# RB_Conn.net
KiCad netlist of a schematic drawn in Altium Designer
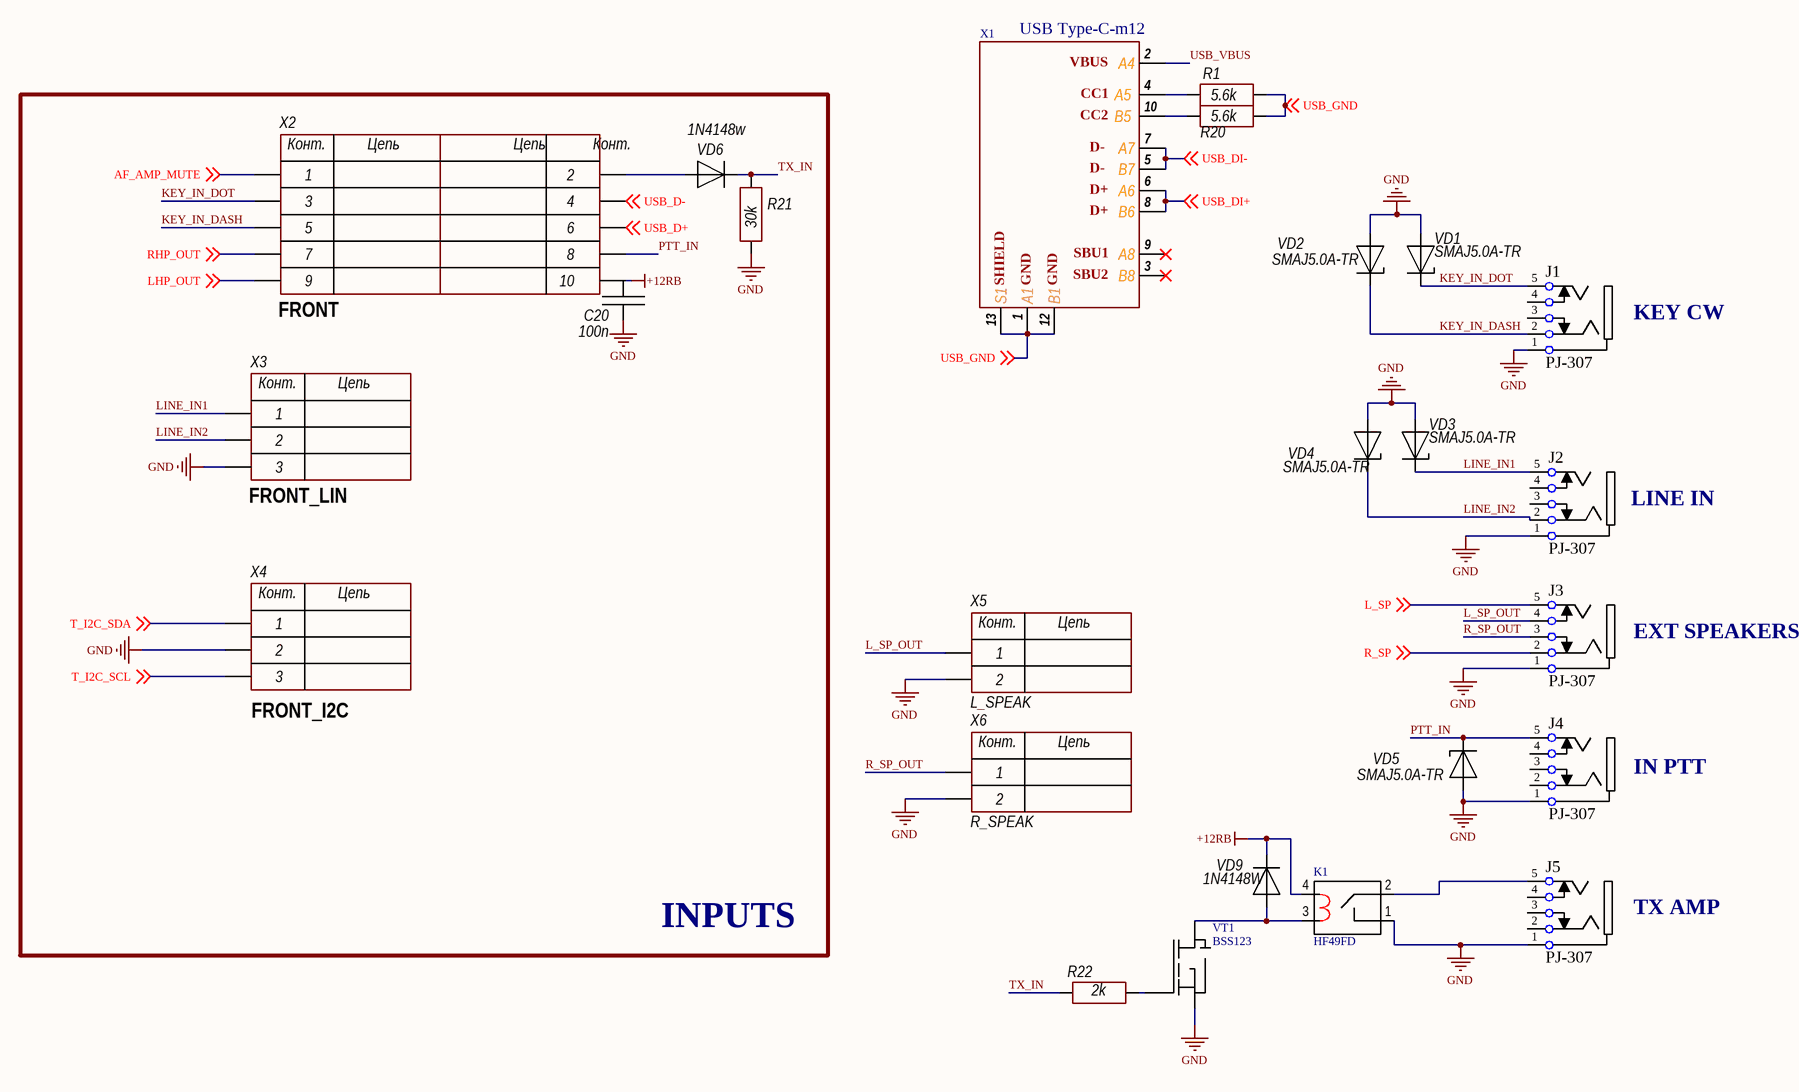
[diagram p0: RB_Conn.SchDoc]

(export (version "E")
  (design (tool "Eeschema 10.0.6"))
  (components
    (comp (ref "C20")
      (value "100n")
      (footprint "standard:CH0805C")
      (libsource (lib "Discrete") (part "Capacitor"))
    )
    (comp (ref "J1")
      (value "PJ-307")
      (footprint "PJ-307")
      (description "KEY")
      (libsource (lib "") (part "JACK_Audio-3_1"))
    )
    (comp (ref "J2")
      (value "PJ-307")
      (footprint "PJ-307")
      (description "LIN")
      (libsource (lib "Connectors") (part "JACK_Audio-3"))
    )
    (comp (ref "J3")
      (value "PJ-307")
      (footprint "PJ-307")
      (description "OUT_SPEAKERS")
      (libsource (lib "Connectors") (part "JACK_Audio-3"))
    )
    (comp (ref "J4")
      (value "PJ-307")
      (footprint "PJ-307")
      (description "PTT_IN")
      (libsource (lib "Connectors") (part "JACK_Audio-3"))
    )
    (comp (ref "J5")
      (value "PJ-307")
      (footprint "PJ-307")
      (description "TX")
      (libsource (lib "Connectors") (part "JACK_Audio-3"))
    )
    (comp (ref "K1") (value "HF49FD") (footprint "HF49FD") (libsource (lib "Relay") (part "HF49FD 012-1H12")))
    (comp (ref "R1")
      (value "5.6k")
      (footprint "standard:CH0805R")
      (libsource (lib "Discrete") (part "Resistor"))
    )
    (comp (ref "R20") (value "5.6k") (footprint "standard:CH0805R") (libsource (lib "") (part "Resistor_1")))
    (comp (ref "R21") (value "30k") (footprint "standard:CH0805R") (libsource (lib "") (part "Resistor_2")))
    (comp (ref "R22")
      (value "2k")
      (footprint "standard:CH0805R")
      (libsource (lib "Discrete") (part "Resistor"))
    )
    (comp (ref "VD1")
      (value "SMAJ5.0A-TR")
      (footprint "standard:SMA")
      (libsource (lib "Diods") (part "Diod Zener"))
    )
    (comp (ref "VD2")
      (value "SMAJ5.0A-TR")
      (footprint "standard:SMA")
      (libsource (lib "Diods") (part "Diod Zener"))
    )
    (comp (ref "VD3")
      (value "SMAJ5.0A-TR")
      (footprint "standard:SMA")
      (libsource (lib "Diods") (part "Diod Zener"))
    )
    (comp (ref "VD4")
      (value "SMAJ5.0A-TR")
      (footprint "standard:SMA")
      (libsource (lib "Diods") (part "Diod Zener"))
    )
    (comp (ref "VD5")
      (value "SMAJ5.0A-TR")
      (footprint "standard:SMA")
      (libsource (lib "Diods") (part "Diod Zener"))
    )
    (comp (ref "VD6") (value "1N4148w") (footprint "standard:SOD323") (libsource (lib "Diods") (part "Diod")))
    (comp (ref "VD9") (value "1N4148W") (footprint "standard:SOD123") (libsource (lib "Diods") (part "Diod")))
    (comp (ref "VT1") (value "BSS123") (footprint "SOT23_132") (libsource (lib "Transistor") (part "BSS123")))
    (comp (ref "X1")
      (value "USB Type-C-m12")
      (footprint "PCBComponent_1")
      (libsource (lib "USB typ-c") (part "USB-C_2.0"))
    )
    (comp (ref "X2")
      (value "FRONT")
      (footprint "custom:CON: BH-10")
      (libsource (lib "Connectors") (part "10(2)-Connector"))
    )
    (comp (ref "X3")
      (value "FRONT_LIN")
      (footprint "custom:CON: CWF-3")
      (libsource (lib "Connectors") (part "3-Connector"))
    )
    (comp (ref "X4")
      (value "FRONT_I2C")
      (footprint "custom:CON: CWF-3")
      (libsource (lib "Connectors") (part "3-Connector"))
    )
    (comp (ref "X5")
      (value "L_SPEAK")
      (footprint "custom:CON: PLS-2")
      (libsource (lib "Connectors") (part "2-Connector"))
    )
    (comp (ref "X6")
      (value "R_SPEAK")
      (footprint "custom:CON: PLS-2")
      (libsource (lib "Connectors") (part "2-Connector"))
    )
  )
  (nets
    (net (code "1") (name "+12RB") (class "Default")
      (node (ref "K1") (pin "4") (pintype "passive"))
      (node (ref "VD9") (pin "2") (pinfunction "2_2") (pintype "passive"))
      (node (ref "X2") (pin "10") (pinfunction "10_10") (pintype "power_in"))
    )
    (net (code "2") (name "/KEY_IN_DASH") (class "Default")
      (node (ref "J1") (pin "2") (pinfunction "2_2") (pintype "passive"))
      (node (ref "VD2") (pin "2") (pinfunction "C_2") (pintype "passive"))
      (node (ref "X2") (pin "5") (pinfunction "5_5") (pintype "power_in"))
    )
    (net (code "3") (name "/KEY_IN_DOT") (class "Default")
      (node (ref "J1") (pin "5") (pinfunction "5_5") (pintype "passive"))
      (node (ref "VD1") (pin "2") (pinfunction "C_2") (pintype "passive"))
      (node (ref "X2") (pin "3") (pinfunction "3_3") (pintype "passive"))
    )
    (net (code "4") (name "/LINE_IN1") (class "Default")
      (node (ref "J2") (pin "5") (pinfunction "5_5") (pintype "passive"))
      (node (ref "VD3") (pin "2") (pinfunction "C_2") (pintype "passive"))
      (node (ref "X3") (pin "1") (pinfunction "1_1") (pintype "passive"))
    )
    (net (code "5") (name "/LINE_IN2") (class "Default")
      (node (ref "J2") (pin "2") (pinfunction "2_2") (pintype "passive"))
      (node (ref "VD4") (pin "2") (pinfunction "C_2") (pintype "passive"))
      (node (ref "X3") (pin "2") (pinfunction "2_2") (pintype "passive"))
    )
    (net (code "6") (name "/L_SP_OUT") (class "Default")
      (node (ref "J3") (pin "4") (pinfunction "4_4") (pintype "passive"))
      (node (ref "X5") (pin "1") (pinfunction "1_1") (pintype "passive"))
    )
    (net (code "7") (name "/PTT_IN") (class "Default")
      (node (ref "J4") (pin "5") (pinfunction "5_5") (pintype "passive"))
      (node (ref "VD5") (pin "2") (pinfunction "C_2") (pintype "passive"))
      (node (ref "X2") (pin "8") (pinfunction "8_8") (pintype "power_in"))
    )
    (net (code "8") (name "/R_SP_OUT") (class "Default")
      (node (ref "J3") (pin "3") (pinfunction "3_3") (pintype "passive"))
      (node (ref "X6") (pin "1") (pinfunction "1_1") (pintype "passive"))
    )
    (net (code "9") (name "/TX_IN") (class "Default")
      (node (ref "R21") (pin "2") (pinfunction "2_2") (pintype "passive"))
      (node (ref "R22") (pin "1") (pinfunction "1_1") (pintype "passive"))
      (node (ref "VD6") (pin "2") (pinfunction "2_2") (pintype "passive"))
    )
    (net (code "10") (name "/USB_VBUS") (class "Default")
      (node (ref "X1") (pin "2") (pinfunction "A4_2") (pintype "power_in"))
    )
    (net (code "11") (name "AF_AMP_MUTE") (class "Default")
      (node (ref "X2") (pin "1") (pinfunction "1_1") (pintype "passive"))
    )
    (net (code "12") (name "GND") (class "Default")
      (node (ref "C20") (pin "1") (pinfunction "1_1") (pintype "power_in"))
      (node (ref "J1") (pin "1") (pinfunction "1_1") (pintype "passive"))
      (node (ref "J2") (pin "1") (pinfunction "1_1") (pintype "passive"))
      (node (ref "J3") (pin "1") (pinfunction "1_1") (pintype "passive"))
      (node (ref "J4") (pin "1") (pinfunction "1_1") (pintype "passive"))
      (node (ref "J5") (pin "1") (pinfunction "1_1") (pintype "passive"))
      (node (ref "K1") (pin "1") (pintype "passive"))
      (node (ref "R21") (pin "1") (pinfunction "1_1") (pintype "passive"))
      (node (ref "VD1") (pin "1") (pinfunction "A_1") (pintype "passive"))
      (node (ref "VD2") (pin "1") (pinfunction "A_1") (pintype "passive"))
      (node (ref "VD3") (pin "1") (pinfunction "A_1") (pintype "passive"))
      (node (ref "VD4") (pin "1") (pinfunction "A_1") (pintype "passive"))
      (node (ref "VD5") (pin "1") (pinfunction "A_1") (pintype "passive"))
      (node (ref "VT1") (pin "2") (pinfunction "S_2") (pintype "passive"))
      (node (ref "X3") (pin "3") (pinfunction "3_3") (pintype "power_in"))
      (node (ref "X4") (pin "2") (pinfunction "2_2") (pintype "passive"))
      (node (ref "X5") (pin "2") (pinfunction "2_2") (pintype "passive"))
      (node (ref "X6") (pin "2") (pinfunction "2_2") (pintype "passive"))
    )
    (net (code "13") (name "LHP_OUT") (class "Default")
      (node (ref "X2") (pin "9") (pinfunction "9_9") (pintype "power_in"))
    )
    (net (code "14") (name "L_SP") (class "Default")
      (node (ref "J3") (pin "5") (pinfunction "5_5") (pintype "passive"))
    )
    (net (code "15") (name "Net-(J5-Pad5)") (class "Default")
      (node (ref "J5") (pin "5") (pinfunction "5_5") (pintype "passive"))
      (node (ref "K1") (pin "2") (pintype "passive"))
    )
    (net (code "16") (name "Net-(VD6-Pad1)") (class "Default")
      (node (ref "VD6") (pin "1") (pinfunction "1_1") (pintype "passive"))
      (node (ref "X2") (pin "2") (pinfunction "2_2") (pintype "passive"))
    )
    (net (code "17") (name "Net-(VT1-D)") (class "Default")
      (node (ref "K1") (pin "3") (pintype "passive"))
      (node (ref "VD9") (pin "1") (pinfunction "1_1") (pintype "passive"))
      (node (ref "VT1") (pin "3") (pinfunction "D_3") (pintype "passive"))
    )
    (net (code "18") (name "Net-(VT1-G)") (class "Default")
      (node (ref "R22") (pin "2") (pinfunction "2_2") (pintype "passive"))
      (node (ref "VT1") (pin "1") (pinfunction "G_1") (pintype "passive"))
    )
    (net (code "19") (name "Net-(X1-A5)") (class "Default")
      (node (ref "R1") (pin "1") (pinfunction "1_1") (pintype "passive"))
      (node (ref "X1") (pin "4") (pinfunction "A5_4") (pintype "power_in"))
    )
    (net (code "20") (name "Net-(X1-B5)") (class "Default")
      (node (ref "R20") (pin "1") (pinfunction "1_1") (pintype "passive"))
      (node (ref "X1") (pin "10") (pinfunction "B5_10") (pintype "power_in"))
    )
    (net (code "21") (name "RHP_OUT") (class "Default")
      (node (ref "X2") (pin "7") (pinfunction "7_7") (pintype "power_in"))
    )
    (net (code "22") (name "R_SP") (class "Default")
      (node (ref "J3") (pin "2") (pinfunction "2_2") (pintype "passive"))
    )
    (net (code "23") (name "T_I2C_SCL") (class "Default")
      (node (ref "X4") (pin "3") (pinfunction "3_3") (pintype "power_in"))
    )
    (net (code "24") (name "T_I2C_SDA") (class "Default")
      (node (ref "X4") (pin "1") (pinfunction "1_1") (pintype "passive"))
    )
    (net (code "25") (name "USB_D+") (class "Default")
      (node (ref "X2") (pin "6") (pinfunction "6_6") (pintype "power_in"))
    )
    (net (code "26") (name "USB_D-") (class "Default")
      (node (ref "X2") (pin "4") (pinfunction "4_4") (pintype "passive"))
    )
    (net (code "27") (name "USB_DI+") (class "Default")
      (node (ref "X1") (pin "6") (pinfunction "A6_6") (pintype "power_in"))
      (node (ref "X1") (pin "8") (pinfunction "B6_8") (pintype "power_in"))
    )
    (net (code "28") (name "USB_DI-") (class "Default")
      (node (ref "X1") (pin "5") (pinfunction "B7_5") (pintype "power_in"))
      (node (ref "X1") (pin "7") (pinfunction "A7_7") (pintype "power_in"))
    )
    (net (code "29") (name "USB_GND") (class "Default")
      (node (ref "R1") (pin "2") (pinfunction "2_2") (pintype "passive"))
      (node (ref "R20") (pin "2") (pinfunction "2_2") (pintype "passive"))
      (node (ref "X1") (pin "1") (pinfunction "A1_1") (pintype "power_in"))
      (node (ref "X1") (pin "12") (pinfunction "B1_12") (pintype "power_in"))
      (node (ref "X1") (pin "13") (pinfunction "S1_13") (pintype "power_in"))
    )
    (net (code "30") (name "unconnected-(C20-Pad2)") (class "Default")
      (node (ref "C20") (pin "2") (pinfunction "2_2") (pintype "power_in"))
    )
    (net (code "31") (name "unconnected-(J1-Pad3)") (class "Default")
      (node (ref "J1") (pin "3") (pinfunction "3_3") (pintype "passive"))
    )
    (net (code "32") (name "unconnected-(J1-Pad4)") (class "Default")
      (node (ref "J1") (pin "4") (pinfunction "4_4") (pintype "passive"))
    )
    (net (code "33") (name "unconnected-(J2-Pad3)") (class "Default")
      (node (ref "J2") (pin "3") (pinfunction "3_3") (pintype "passive"))
    )
    (net (code "34") (name "unconnected-(J2-Pad4)") (class "Default")
      (node (ref "J2") (pin "4") (pinfunction "4_4") (pintype "passive"))
    )
    (net (code "35") (name "unconnected-(J4-Pad2)") (class "Default")
      (node (ref "J4") (pin "2") (pinfunction "2_2") (pintype "passive"))
    )
    (net (code "36") (name "unconnected-(J4-Pad3)") (class "Default")
      (node (ref "J4") (pin "3") (pinfunction "3_3") (pintype "passive"))
    )
    (net (code "37") (name "unconnected-(J4-Pad4)") (class "Default")
      (node (ref "J4") (pin "4") (pinfunction "4_4") (pintype "passive"))
    )
    (net (code "38") (name "unconnected-(J5-Pad2)") (class "Default")
      (node (ref "J5") (pin "2") (pinfunction "2_2") (pintype "passive"))
    )
    (net (code "39") (name "unconnected-(J5-Pad3)") (class "Default")
      (node (ref "J5") (pin "3") (pinfunction "3_3") (pintype "passive"))
    )
    (net (code "40") (name "unconnected-(J5-Pad4)") (class "Default")
      (node (ref "J5") (pin "4") (pinfunction "4_4") (pintype "passive"))
    )
    (net (code "41") (name "unconnected-(X1-A8-Pad9)") (class "Default")
      (node (ref "X1") (pin "9") (pinfunction "A8_9") (pintype "power_in+no_connect"))
    )
    (net (code "42") (name "unconnected-(X1-B8-Pad3)") (class "Default")
      (node (ref "X1") (pin "3") (pinfunction "B8_3") (pintype "power_in+no_connect"))
    )
  )
)
